# Filter_Section.net
KiCad netlist of a schematic drawn in Altium Designer
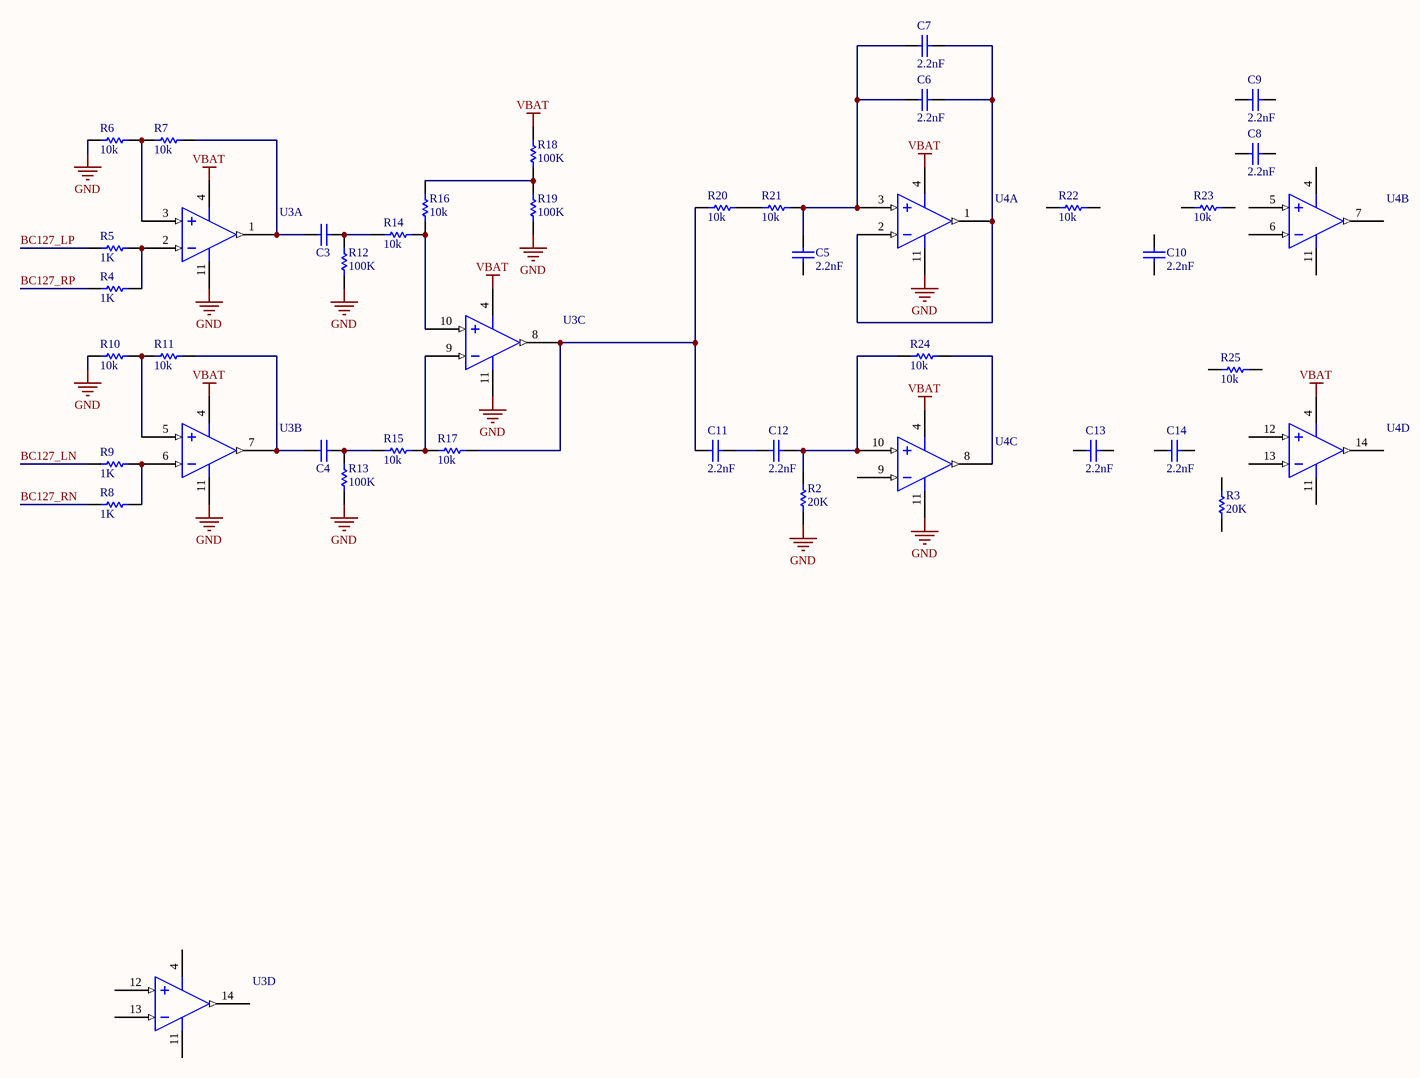
[diagram p0: Filter Section.SchDoc]

(export (version "E")
  (design (tool "Eeschema 10.0.6"))
  (components
    (comp (ref "C3")
      (value "1uf")
      (fields
        (field (name "DIGIKEY PART NUMBER") "495-1119-ND")
        (field (name "MANUFACTURER") "EPCOS (TDK)")
        (field (name "VOLTAGE") "63V")
      )
      (libsource (lib "Speaker Library") (part "CAP Radial 5mm"))
    )
    (comp (ref "C4")
      (value "1uf")
      (fields
        (field (name "DIGIKEY PART NUMBER") "495-1119-ND")
        (field (name "MANUFACTURER") "EPCOS (TDK)")
        (field (name "VOLTAGE") "63V")
      )
      (libsource (lib "Speaker Library") (part "CAP Radial 5mm"))
    )
    (comp (ref "C5")
      (value "2.2nF")
      (footprint "CAPC1608X09N")
      (description "Capacitor 2.2nF 0603")
      (fields (field (name "DIGIKEY PART NUMBER") "PCF1300CT-ND"))
      (libsource (lib "Speaker Library") (part "CAP 2.2nF 0603"))
    )
    (comp (ref "C6")
      (value "2.2nF")
      (footprint "CAPC1608X09N")
      (description "Capacitor 2.2nF 0603")
      (fields (field (name "DIGIKEY PART NUMBER") "PCF1300CT-ND"))
      (libsource (lib "Speaker Library") (part "CAP 2.2nF 0603"))
    )
    (comp (ref "C7")
      (value "2.2nF")
      (footprint "CAPC1608X09N")
      (description "Capacitor 2.2nF 0603")
      (fields (field (name "DIGIKEY PART NUMBER") "PCF1300CT-ND"))
      (libsource (lib "Speaker Library") (part "CAP 2.2nF 0603"))
    )
    (comp (ref "C8")
      (value "2.2nF")
      (footprint "CAPC1608X09N")
      (description "Capacitor 2.2nF 0603")
      (fields (field (name "DIGIKEY PART NUMBER") "PCF1300CT-ND"))
      (libsource (lib "Speaker Library") (part "CAP 2.2nF 0603"))
    )
    (comp (ref "C9")
      (value "2.2nF")
      (footprint "CAPC1608X09N")
      (description "Capacitor 2.2nF 0603")
      (fields (field (name "DIGIKEY PART NUMBER") "PCF1300CT-ND"))
      (libsource (lib "Speaker Library") (part "CAP 2.2nF 0603"))
    )
    (comp (ref "C10")
      (value "2.2nF")
      (footprint "CAPC1608X09N")
      (description "Capacitor 2.2nF 0603")
      (fields (field (name "DIGIKEY PART NUMBER") "PCF1300CT-ND"))
      (libsource (lib "Speaker Library") (part "CAP 2.2nF 0603"))
    )
    (comp (ref "C11")
      (value "2.2nF")
      (footprint "CAPC1608X09N")
      (description "Capacitor 2.2nF 0603")
      (fields (field (name "DIGIKEY PART NUMBER") "PCF1300CT-ND"))
      (libsource (lib "Speaker Library") (part "CAP 2.2nF 0603"))
    )
    (comp (ref "C12")
      (value "2.2nF")
      (footprint "CAPC1608X09N")
      (description "Capacitor 2.2nF 0603")
      (fields (field (name "DIGIKEY PART NUMBER") "PCF1300CT-ND"))
      (libsource (lib "Speaker Library") (part "CAP 2.2nF 0603"))
    )
    (comp (ref "C13")
      (value "2.2nF")
      (footprint "CAPC1608X09N")
      (description "Capacitor 2.2nF 0603")
      (fields (field (name "DIGIKEY PART NUMBER") "PCF1300CT-ND"))
      (libsource (lib "Speaker Library") (part "CAP 2.2nF 0603"))
    )
    (comp (ref "C14")
      (value "2.2nF")
      (footprint "CAPC1608X09N")
      (description "Capacitor 2.2nF 0603")
      (fields (field (name "DIGIKEY PART NUMBER") "PCF1300CT-ND"))
      (libsource (lib "Speaker Library") (part "CAP 2.2nF 0603"))
    )
    (comp (ref "R2")
      (value "20K")
      (footprint "RESC1608X06N")
      (fields (field (name "TOLERANCE") "1%") (field (name "POWER") "0.1W"))
      (libsource (lib "Speaker Library") (part "RES 20K 0603"))
    )
    (comp (ref "R3")
      (value "20K")
      (footprint "RESC1608X06N")
      (fields (field (name "TOLERANCE") "1%") (field (name "POWER") "0.1W"))
      (libsource (lib "Speaker Library") (part "RES 20K 0603"))
    )
    (comp (ref "R4")
      (value "1K")
      (footprint "RESC1608X06N")
      (fields
        (field (name "TOLERANCE") "1%")
        (field (name "POWER") "0.25W")
        (field (name "MANUFACTURER") "Panasonic")
      )
      (libsource (lib "Speaker Library") (part "RES 1K 0603"))
    )
    (comp (ref "R5")
      (value "1K")
      (footprint "RESC1608X06N")
      (fields
        (field (name "TOLERANCE") "1%")
        (field (name "POWER") "0.25W")
        (field (name "MANUFACTURER") "Panasonic")
      )
      (libsource (lib "Speaker Library") (part "RES 1K 0603"))
    )
    (comp (ref "R6")
      (value "10k")
      (footprint "RESC1608X06N")
      (fields
        (field (name "TOLERANCE") "1%")
        (field (name "POWER") "0.1W")
        (field (name "MANUFACTURER") "Yageo")
      )
      (libsource (lib "Speaker Library") (part "RES 10K 0603"))
    )
    (comp (ref "R7")
      (value "10k")
      (footprint "RESC1608X06N")
      (fields
        (field (name "TOLERANCE") "1%")
        (field (name "POWER") "0.1W")
        (field (name "MANUFACTURER") "Yageo")
      )
      (libsource (lib "Speaker Library") (part "RES 10K 0603"))
    )
    (comp (ref "R8")
      (value "1K")
      (footprint "RESC1608X06N")
      (fields
        (field (name "TOLERANCE") "1%")
        (field (name "POWER") "0.25W")
        (field (name "MANUFACTURER") "Panasonic")
      )
      (libsource (lib "Speaker Library") (part "RES 1K 0603"))
    )
    (comp (ref "R9")
      (value "1K")
      (footprint "RESC1608X06N")
      (fields
        (field (name "TOLERANCE") "1%")
        (field (name "POWER") "0.25W")
        (field (name "MANUFACTURER") "Panasonic")
      )
      (libsource (lib "Speaker Library") (part "RES 1K 0603"))
    )
    (comp (ref "R10")
      (value "10k")
      (footprint "RESC1608X06N")
      (fields
        (field (name "TOLERANCE") "1%")
        (field (name "POWER") "0.1W")
        (field (name "MANUFACTURER") "Yageo")
      )
      (libsource (lib "Speaker Library") (part "RES 10K 0603"))
    )
    (comp (ref "R11")
      (value "10k")
      (footprint "RESC1608X06N")
      (fields
        (field (name "TOLERANCE") "1%")
        (field (name "POWER") "0.1W")
        (field (name "MANUFACTURER") "Yageo")
      )
      (libsource (lib "Speaker Library") (part "RES 10K 0603"))
    )
    (comp (ref "R12")
      (value "100K")
      (footprint "RESC1608X06N")
      (fields (field (name "TOLERANCE") "1%") (field (name "POWER") "0.1W"))
      (libsource (lib "Speaker Library") (part "RES 100K 0603"))
    )
    (comp (ref "R13")
      (value "100K")
      (footprint "RESC1608X06N")
      (fields (field (name "TOLERANCE") "1%") (field (name "POWER") "0.1W"))
      (libsource (lib "Speaker Library") (part "RES 100K 0603"))
    )
    (comp (ref "R14")
      (value "10k")
      (footprint "RESC1608X06N")
      (fields
        (field (name "TOLERANCE") "1%")
        (field (name "POWER") "0.1W")
        (field (name "MANUFACTURER") "Yageo")
      )
      (libsource (lib "Speaker Library") (part "RES 10K 0603"))
    )
    (comp (ref "R15")
      (value "10k")
      (footprint "RESC1608X06N")
      (fields
        (field (name "TOLERANCE") "1%")
        (field (name "POWER") "0.1W")
        (field (name "MANUFACTURER") "Yageo")
      )
      (libsource (lib "Speaker Library") (part "RES 10K 0603"))
    )
    (comp (ref "R16")
      (value "10k")
      (footprint "RESC1608X06N")
      (fields
        (field (name "TOLERANCE") "1%")
        (field (name "POWER") "0.1W")
        (field (name "MANUFACTURER") "Yageo")
      )
      (libsource (lib "Speaker Library") (part "RES 10K 0603"))
    )
    (comp (ref "R17")
      (value "10k")
      (footprint "RESC1608X06N")
      (fields
        (field (name "TOLERANCE") "1%")
        (field (name "POWER") "0.1W")
        (field (name "MANUFACTURER") "Yageo")
      )
      (libsource (lib "Speaker Library") (part "RES 10K 0603"))
    )
    (comp (ref "R18")
      (value "100K")
      (footprint "RESC1608X06N")
      (fields (field (name "TOLERANCE") "1%") (field (name "POWER") "0.1W"))
      (libsource (lib "Speaker Library") (part "RES 100K 0603"))
    )
    (comp (ref "R19")
      (value "100K")
      (footprint "RESC1608X06N")
      (fields (field (name "TOLERANCE") "1%") (field (name "POWER") "0.1W"))
      (libsource (lib "Speaker Library") (part "RES 100K 0603"))
    )
    (comp (ref "R20")
      (value "10k")
      (footprint "RESC1608X06N")
      (fields
        (field (name "TOLERANCE") "1%")
        (field (name "POWER") "0.1W")
        (field (name "MANUFACTURER") "Yageo")
      )
      (libsource (lib "Speaker Library") (part "RES 10K 0603"))
    )
    (comp (ref "R21")
      (value "10k")
      (footprint "RESC1608X06N")
      (fields
        (field (name "TOLERANCE") "1%")
        (field (name "POWER") "0.1W")
        (field (name "MANUFACTURER") "Yageo")
      )
      (libsource (lib "Speaker Library") (part "RES 10K 0603"))
    )
    (comp (ref "R22")
      (value "10k")
      (footprint "RESC1608X06N")
      (fields
        (field (name "TOLERANCE") "1%")
        (field (name "POWER") "0.1W")
        (field (name "MANUFACTURER") "Yageo")
      )
      (libsource (lib "Speaker Library") (part "RES 10K 0603"))
    )
    (comp (ref "R23")
      (value "10k")
      (footprint "RESC1608X06N")
      (fields
        (field (name "TOLERANCE") "1%")
        (field (name "POWER") "0.1W")
        (field (name "MANUFACTURER") "Yageo")
      )
      (libsource (lib "Speaker Library") (part "RES 10K 0603"))
    )
    (comp (ref "R24")
      (value "10k")
      (footprint "RESC1608X06N")
      (fields
        (field (name "TOLERANCE") "1%")
        (field (name "POWER") "0.1W")
        (field (name "MANUFACTURER") "Yageo")
      )
      (libsource (lib "Speaker Library") (part "RES 10K 0603"))
    )
    (comp (ref "R25")
      (value "10k")
      (footprint "RESC1608X06N")
      (fields
        (field (name "TOLERANCE") "1%")
        (field (name "POWER") "0.1W")
        (field (name "MANUFACTURER") "Yageo")
      )
      (libsource (lib "Speaker Library") (part "RES 10K 0603"))
    )
    (comp (ref "U3")
      (value "OPA4134UA")
      (footprint "SOIC127P600X175-14N")
      (description "Quad OPAx134 Operational Amplifier")
      (libsource (lib "Speaker Library") (part "OPA4134UA"))
    )
    (comp (ref "U4")
      (value "OPA4134UA")
      (footprint "SOIC127P600X175-14N")
      (description "Quad OPAx134 Operational Amplifier")
      (libsource (lib "Speaker Library") (part "OPA4134UA"))
    )
  )
  (nets
    (net (code "1") (name "/BC127_LN") (class "Default")
      (node (ref "R9") (pin "1") (pinfunction "1_1") (pintype "passive"))
    )
    (net (code "2") (name "/BC127_LP") (class "Default")
      (node (ref "R5") (pin "1") (pinfunction "1_1") (pintype "passive"))
    )
    (net (code "3") (name "/BC127_RN") (class "Default")
      (node (ref "R8") (pin "1") (pinfunction "1_1") (pintype "passive"))
    )
    (net (code "4") (name "/BC127_RP") (class "Default")
      (node (ref "R4") (pin "1") (pinfunction "1_1") (pintype "passive"))
    )
    (net (code "5") (name "GND") (class "Default")
      (node (ref "R10") (pin "1") (pinfunction "1_1") (pintype "passive"))
      (node (ref "R12") (pin "1") (pinfunction "1_1") (pintype "passive"))
      (node (ref "R13") (pin "1") (pinfunction "1_1") (pintype "passive"))
      (node (ref "R19") (pin "1") (pinfunction "1_1") (pintype "passive"))
      (node (ref "R2") (pin "1") (pinfunction "1_1") (pintype "passive"))
      (node (ref "R6") (pin "1") (pinfunction "1_1") (pintype "passive"))
    )
    (net (code "6") (name "Net-(C3-Pad2)") (class "Default")
      (node (ref "C3") (pin "2") (pinfunction "2_2") (pintype "passive"))
      (node (ref "R12") (pin "2") (pinfunction "2_2") (pintype "passive"))
      (node (ref "R14") (pin "1") (pinfunction "1_1") (pintype "passive"))
    )
    (net (code "7") (name "Net-(C4-Pad2)") (class "Default")
      (node (ref "C4") (pin "2") (pinfunction "2_2") (pintype "passive"))
      (node (ref "R13") (pin "2") (pinfunction "2_2") (pintype "passive"))
      (node (ref "R15") (pin "1") (pinfunction "1_1") (pintype "passive"))
    )
    (net (code "8") (name "Net-(C11-Pad2)") (class "Default")
      (node (ref "C11") (pin "2") (pinfunction "2_2") (pintype "passive"))
      (node (ref "C12") (pin "1") (pinfunction "1_1") (pintype "passive"))
    )
    (net (code "9") (name "Net-(R16-Pad2)") (class "Default")
      (node (ref "R16") (pin "2") (pinfunction "2_2") (pintype "passive"))
      (node (ref "R18") (pin "1") (pinfunction "1_1") (pintype "passive"))
      (node (ref "R19") (pin "2") (pinfunction "2_2") (pintype "passive"))
    )
    (net (code "10") (name "Net-(R20-Pad2)") (class "Default")
      (node (ref "R20") (pin "2") (pinfunction "2_2") (pintype "passive"))
      (node (ref "R21") (pin "1") (pinfunction "1_1") (pintype "passive"))
    )
    (net (code "11") (name "Net-(U3A-+In_A)") (class "Default")
      (node (ref "R6") (pin "2") (pinfunction "2_2") (pintype "passive"))
      (node (ref "R7") (pin "1") (pinfunction "1_1") (pintype "passive"))
      (node (ref "U3") (pin "3") (pinfunction "+In_A_3") (pintype "input"))
    )
    (net (code "12") (name "Net-(U3A--In_A)") (class "Default")
      (node (ref "R4") (pin "2") (pinfunction "2_2") (pintype "passive"))
      (node (ref "R5") (pin "2") (pinfunction "2_2") (pintype "passive"))
      (node (ref "U3") (pin "2") (pinfunction "-In_A_2") (pintype "input"))
    )
    (net (code "13") (name "Net-(U3A-Out_A)") (class "Default")
      (node (ref "C3") (pin "1") (pinfunction "1_1") (pintype "passive"))
      (node (ref "R7") (pin "2") (pinfunction "2_2") (pintype "passive"))
      (node (ref "U3") (pin "1") (pinfunction "Out_A_1") (pintype "output"))
    )
    (net (code "14") (name "Net-(U3B-+In_B)") (class "Default")
      (node (ref "R10") (pin "2") (pinfunction "2_2") (pintype "passive"))
      (node (ref "R11") (pin "1") (pinfunction "1_1") (pintype "passive"))
      (node (ref "U3") (pin "5") (pinfunction "+In_B_5") (pintype "input"))
    )
    (net (code "15") (name "Net-(U3B--In_B)") (class "Default")
      (node (ref "R8") (pin "2") (pinfunction "2_2") (pintype "passive"))
      (node (ref "R9") (pin "2") (pinfunction "2_2") (pintype "passive"))
      (node (ref "U3") (pin "6") (pinfunction "-In_B_6") (pintype "input"))
    )
    (net (code "16") (name "Net-(U3B-Out_B)") (class "Default")
      (node (ref "C4") (pin "1") (pinfunction "1_1") (pintype "passive"))
      (node (ref "R11") (pin "2") (pinfunction "2_2") (pintype "passive"))
      (node (ref "U3") (pin "7") (pinfunction "Out_B_7") (pintype "output"))
    )
    (net (code "17") (name "Net-(U3C-+In_C)") (class "Default")
      (node (ref "R14") (pin "2") (pinfunction "2_2") (pintype "passive"))
      (node (ref "R16") (pin "1") (pinfunction "1_1") (pintype "passive"))
      (node (ref "U3") (pin "10") (pinfunction "+In_C_10") (pintype "input"))
    )
    (net (code "18") (name "Net-(U3C--In_C)") (class "Default")
      (node (ref "R15") (pin "2") (pinfunction "2_2") (pintype "passive"))
      (node (ref "R17") (pin "2") (pinfunction "2_2") (pintype "passive"))
      (node (ref "U3") (pin "9") (pinfunction "-In_C_9") (pintype "input"))
    )
    (net (code "19") (name "Net-(U3C-Out_C)") (class "Default")
      (node (ref "C11") (pin "1") (pinfunction "1_1") (pintype "passive"))
      (node (ref "R17") (pin "1") (pinfunction "1_1") (pintype "passive"))
      (node (ref "R20") (pin "1") (pinfunction "1_1") (pintype "passive"))
      (node (ref "U3") (pin "8") (pinfunction "Out_C_8") (pintype "output"))
    )
    (net (code "20") (name "Net-(U4A-+In_A)") (class "Default")
      (node (ref "C5") (pin "2") (pinfunction "2_2") (pintype "passive"))
      (node (ref "C6") (pin "1") (pinfunction "1_1") (pintype "passive"))
      (node (ref "C7") (pin "1") (pinfunction "1_1") (pintype "passive"))
      (node (ref "R21") (pin "2") (pinfunction "2_2") (pintype "passive"))
      (node (ref "U4") (pin "3") (pinfunction "+In_A_3") (pintype "input"))
    )
    (net (code "21") (name "Net-(U4A--In_A)") (class "Default")
      (node (ref "C6") (pin "2") (pinfunction "2_2") (pintype "passive"))
      (node (ref "C7") (pin "2") (pinfunction "2_2") (pintype "passive"))
      (node (ref "U4") (pin "1") (pinfunction "Out_A_1") (pintype "output"))
      (node (ref "U4") (pin "2") (pinfunction "-In_A_2") (pintype "input"))
    )
    (net (code "22") (name "Net-(U4C-+In_C)") (class "Default")
      (node (ref "C12") (pin "2") (pinfunction "2_2") (pintype "passive"))
      (node (ref "R2") (pin "2") (pinfunction "2_2") (pintype "passive"))
      (node (ref "R24") (pin "1") (pinfunction "1_1") (pintype "passive"))
      (node (ref "U4") (pin "10") (pinfunction "+In_C_10") (pintype "input"))
    )
    (net (code "23") (name "Net-(U4C-Out_C)") (class "Default")
      (node (ref "R24") (pin "2") (pinfunction "2_2") (pintype "passive"))
      (node (ref "U4") (pin "8") (pinfunction "Out_C_8") (pintype "output"))
    )
    (net (code "24") (name "VBAT") (class "Default")
      (node (ref "R18") (pin "2") (pinfunction "2_2") (pintype "passive"))
    )
    (net (code "25") (name "unconnected-(C5-Pad1)") (class "Default")
      (node (ref "C5") (pin "1") (pinfunction "1_1") (pintype "passive"))
    )
    (net (code "26") (name "unconnected-(C8-Pad1)") (class "Default")
      (node (ref "C8") (pin "1") (pinfunction "1_1") (pintype "passive"))
    )
    (net (code "27") (name "unconnected-(C8-Pad2)") (class "Default")
      (node (ref "C8") (pin "2") (pinfunction "2_2") (pintype "passive"))
    )
    (net (code "28") (name "unconnected-(C9-Pad1)") (class "Default")
      (node (ref "C9") (pin "1") (pinfunction "1_1") (pintype "passive"))
    )
    (net (code "29") (name "unconnected-(C9-Pad2)") (class "Default")
      (node (ref "C9") (pin "2") (pinfunction "2_2") (pintype "passive"))
    )
    (net (code "30") (name "unconnected-(C10-Pad1)") (class "Default")
      (node (ref "C10") (pin "1") (pinfunction "1_1") (pintype "passive"))
    )
    (net (code "31") (name "unconnected-(C10-Pad2)") (class "Default")
      (node (ref "C10") (pin "2") (pinfunction "2_2") (pintype "passive"))
    )
    (net (code "32") (name "unconnected-(C13-Pad1)") (class "Default")
      (node (ref "C13") (pin "1") (pinfunction "1_1") (pintype "passive"))
    )
    (net (code "33") (name "unconnected-(C13-Pad2)") (class "Default")
      (node (ref "C13") (pin "2") (pinfunction "2_2") (pintype "passive"))
    )
    (net (code "34") (name "unconnected-(C14-Pad1)") (class "Default")
      (node (ref "C14") (pin "1") (pinfunction "1_1") (pintype "passive"))
    )
    (net (code "35") (name "unconnected-(C14-Pad2)") (class "Default")
      (node (ref "C14") (pin "2") (pinfunction "2_2") (pintype "passive"))
    )
    (net (code "36") (name "unconnected-(R3-Pad1)") (class "Default")
      (node (ref "R3") (pin "1") (pinfunction "1_1") (pintype "passive"))
    )
    (net (code "37") (name "unconnected-(R3-Pad2)") (class "Default")
      (node (ref "R3") (pin "2") (pinfunction "2_2") (pintype "passive"))
    )
    (net (code "38") (name "unconnected-(R22-Pad1)") (class "Default")
      (node (ref "R22") (pin "1") (pinfunction "1_1") (pintype "passive"))
    )
    (net (code "39") (name "unconnected-(R22-Pad2)") (class "Default")
      (node (ref "R22") (pin "2") (pinfunction "2_2") (pintype "passive"))
    )
    (net (code "40") (name "unconnected-(R23-Pad1)") (class "Default")
      (node (ref "R23") (pin "1") (pinfunction "1_1") (pintype "passive"))
    )
    (net (code "41") (name "unconnected-(R23-Pad2)") (class "Default")
      (node (ref "R23") (pin "2") (pinfunction "2_2") (pintype "passive"))
    )
    (net (code "42") (name "unconnected-(R25-Pad1)") (class "Default")
      (node (ref "R25") (pin "1") (pinfunction "1_1") (pintype "passive"))
    )
    (net (code "43") (name "unconnected-(R25-Pad2)") (class "Default")
      (node (ref "R25") (pin "2") (pinfunction "2_2") (pintype "passive"))
    )
    (net (code "44") (name "unconnected-(U3A-V+-Pad4)") (class "Default")
      (node (ref "U3") (pin "4") (pinfunction "V+_4") (pintype "power_in"))
    )
    (net (code "45") (name "unconnected-(U3A-V--Pad11)") (class "Default")
      (node (ref "U3") (pin "11") (pinfunction "V-_11") (pintype "power_in"))
    )
    (net (code "46") (name "unconnected-(U3B-V+-Pad4)") (class "Default")
      (node (ref "U3") (pin "4") (pinfunction "V+_4") (pintype "power_in"))
    )
    (net (code "47") (name "unconnected-(U3B-V+-Pad11)") (class "Default")
      (node (ref "U3") (pin "11") (pinfunction "V+_11") (pintype "power_in"))
    )
    (net (code "48") (name "unconnected-(U3C-V+-Pad4)") (class "Default")
      (node (ref "U3") (pin "4") (pinfunction "V+_4") (pintype "power_in"))
    )
    (net (code "49") (name "unconnected-(U3C-V--Pad11)") (class "Default")
      (node (ref "U3") (pin "11") (pinfunction "V-_11") (pintype "power_in"))
    )
    (net (code "50") (name "unconnected-(U3D-+In_D-Pad12)") (class "Default")
      (node (ref "U3") (pin "12") (pinfunction "+In_D_12") (pintype "input"))
    )
    (net (code "51") (name "unconnected-(U3D--In_D-Pad13)") (class "Default")
      (node (ref "U3") (pin "13") (pinfunction "-In_D_13") (pintype "input"))
    )
    (net (code "52") (name "unconnected-(U3D-Out_D-Pad14)") (class "Default")
      (node (ref "U3") (pin "14") (pinfunction "Out_D_14") (pintype "output"))
    )
    (net (code "53") (name "unconnected-(U3D-V+-Pad4)") (class "Default")
      (node (ref "U3") (pin "4") (pinfunction "V+_4") (pintype "power_in"))
    )
    (net (code "54") (name "unconnected-(U3D-V--Pad11)") (class "Default")
      (node (ref "U3") (pin "11") (pinfunction "V-_11") (pintype "power_in"))
    )
    (net (code "55") (name "unconnected-(U4A-V+-Pad4)") (class "Default")
      (node (ref "U4") (pin "4") (pinfunction "V+_4") (pintype "power_in"))
    )
    (net (code "56") (name "unconnected-(U4A-V--Pad11)") (class "Default")
      (node (ref "U4") (pin "11") (pinfunction "V-_11") (pintype "power_in"))
    )
    (net (code "57") (name "unconnected-(U4B-+In_B-Pad5)") (class "Default")
      (node (ref "U4") (pin "5") (pinfunction "+In_B_5") (pintype "input"))
    )
    (net (code "58") (name "unconnected-(U4B--In_B-Pad6)") (class "Default")
      (node (ref "U4") (pin "6") (pinfunction "-In_B_6") (pintype "input"))
    )
    (net (code "59") (name "unconnected-(U4B-Out_B-Pad7)") (class "Default")
      (node (ref "U4") (pin "7") (pinfunction "Out_B_7") (pintype "output"))
    )
    (net (code "60") (name "unconnected-(U4B-V+-Pad4)") (class "Default")
      (node (ref "U4") (pin "4") (pinfunction "V+_4") (pintype "power_in"))
    )
    (net (code "61") (name "unconnected-(U4B-V+-Pad11)") (class "Default")
      (node (ref "U4") (pin "11") (pinfunction "V+_11") (pintype "power_in"))
    )
    (net (code "62") (name "unconnected-(U4C--In_C-Pad9)") (class "Default")
      (node (ref "U4") (pin "9") (pinfunction "-In_C_9") (pintype "input"))
    )
    (net (code "63") (name "unconnected-(U4C-V+-Pad4)") (class "Default")
      (node (ref "U4") (pin "4") (pinfunction "V+_4") (pintype "power_in"))
    )
    (net (code "64") (name "unconnected-(U4C-V--Pad11)") (class "Default")
      (node (ref "U4") (pin "11") (pinfunction "V-_11") (pintype "power_in"))
    )
    (net (code "65") (name "unconnected-(U4D-+In_D-Pad12)") (class "Default")
      (node (ref "U4") (pin "12") (pinfunction "+In_D_12") (pintype "input"))
    )
    (net (code "66") (name "unconnected-(U4D--In_D-Pad13)") (class "Default")
      (node (ref "U4") (pin "13") (pinfunction "-In_D_13") (pintype "input"))
    )
    (net (code "67") (name "unconnected-(U4D-Out_D-Pad14)") (class "Default")
      (node (ref "U4") (pin "14") (pinfunction "Out_D_14") (pintype "output"))
    )
    (net (code "68") (name "unconnected-(U4D-V+-Pad4)") (class "Default")
      (node (ref "U4") (pin "4") (pinfunction "V+_4") (pintype "power_in"))
    )
    (net (code "69") (name "unconnected-(U4D-V--Pad11)") (class "Default")
      (node (ref "U4") (pin "11") (pinfunction "V-_11") (pintype "power_in"))
    )
  )
)
